# robot_board.net
KiCad netlist of a schematic drawn in EAGLE
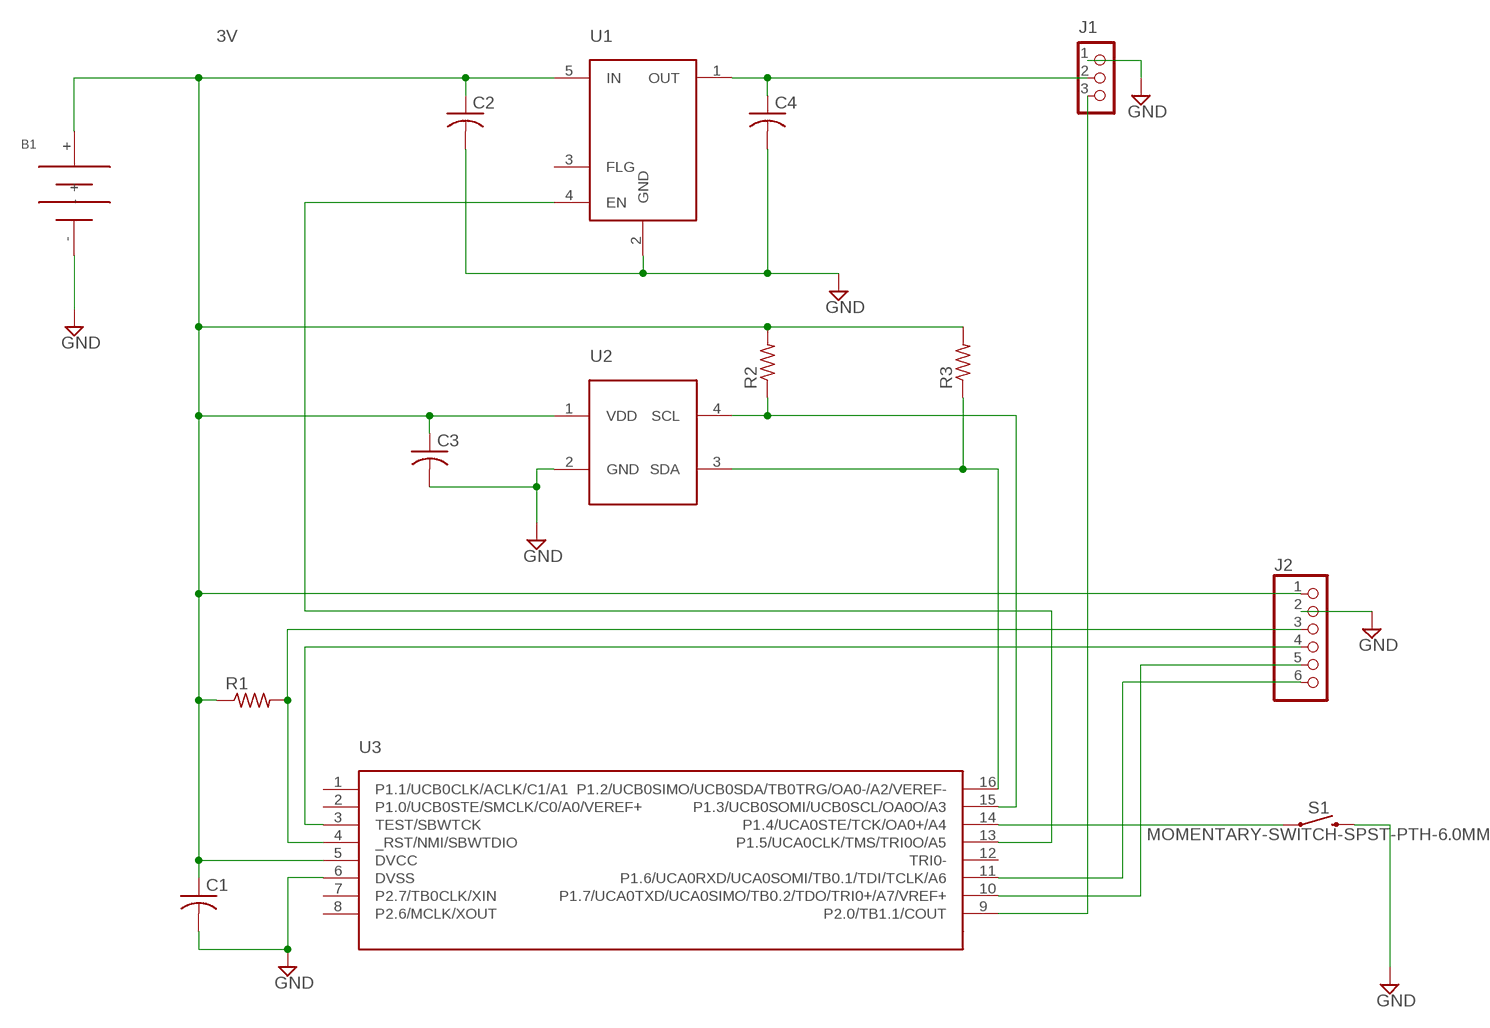
[diagram p0: schematic, sheet 1]

(export (version "E")
  (design (tool "Eeschema 10.0.6"))
  (components
    (comp (ref "B1")
      (value "2XAAA_HOLDER")
      (footprint "eagle-import:CHEAP_ASS_CHINESE_BH")
      (libsource (lib "eagle-import") (part "2XAAA_HOLDER"))
    )
    (comp (ref "C1")
      (value "C-USC0805")
      (footprint "eagle-import:C0805")
      (libsource (lib "eagle-import") (part "C-USC0805"))
    )
    (comp (ref "C2")
      (value "C-USC0805")
      (footprint "eagle-import:C0805")
      (libsource (lib "eagle-import") (part "C-USC0805"))
    )
    (comp (ref "C3")
      (value "C-USC0805")
      (footprint "eagle-import:C0805")
      (libsource (lib "eagle-import") (part "C-USC0805"))
    )
    (comp (ref "C4")
      (value "C-USC0805")
      (footprint "eagle-import:C0805")
      (libsource (lib "eagle-import") (part "C-USC0805"))
    )
    (comp (ref "J1")
      (value "CON_HEADER_1X03-PTH_RIGHT_ANGLED")
      (footprint "eagle-import:M1X3_MALE_RIGHT_ANGLED")
      (libsource (lib "eagle-import") (part "CON_HEADER_1X03-PTH_RIGHT_ANGLED"))
    )
    (comp (ref "J2")
      (value "PINHD-1X6")
      (footprint "eagle-import:1X06")
      (libsource (lib "eagle-import") (part "PINHD-1X6"))
    )
    (comp (ref "R1")
      (value "R-US_R0805")
      (footprint "eagle-import:R0805")
      (libsource (lib "eagle-import") (part "R-US_R0805"))
    )
    (comp (ref "R2")
      (value "R-US_R0805")
      (footprint "eagle-import:R0805")
      (libsource (lib "eagle-import") (part "R-US_R0805"))
    )
    (comp (ref "R3")
      (value "R-US_R0805")
      (footprint "eagle-import:R0805")
      (libsource (lib "eagle-import") (part "R-US_R0805"))
    )
    (comp (ref "S1")
      (value "MOMENTARY-SWITCH-SPST-PTH-6.0MM")
      (footprint "eagle-import:TACTILE_SWITCH_PTH_6.0MM")
      (libsource (lib "eagle-import") (part "MOMENTARY-SWITCH-SPST-PTH-6.0MM"))
    )
    (comp (ref "U1")
      (value "DI_AP22802AW5-7")
      (footprint "eagle-import:SOT-25")
      (libsource (lib "eagle-import") (part "DI_AP22802AW5-7"))
    )
    (comp (ref "U2")
      (value "LITE-ON_LTR-329ALS-01")
      (footprint "eagle-import:LITE-ON_LTR-329ALS-01")
      (libsource (lib "eagle-import") (part "LITE-ON_LTR-329ALS-01"))
    )
    (comp (ref "U3")
      (value "TI_MSP430FR2310IPW16R")
      (footprint "eagle-import:PW_R-PDSO-G16")
      (libsource (lib "eagle-import") (part "TI_MSP430FR2310IPW16R"))
    )
  )
  (nets
    (net (code "1") (name "/3V") (class "Default")
      (node (ref "B1") (pin "+") (pinfunction "+_+") (pintype "bidirectional"))
      (node (ref "C1") (pin "1") (pinfunction "1_1") (pintype "passive"))
      (node (ref "C2") (pin "1") (pinfunction "1_1") (pintype "passive"))
      (node (ref "C3") (pin "1") (pinfunction "1_1") (pintype "passive"))
      (node (ref "J2") (pin "1") (pinfunction "1_1") (pintype "passive"))
      (node (ref "R1") (pin "1") (pinfunction "1_1") (pintype "passive"))
      (node (ref "R2") (pin "2") (pinfunction "2_2") (pintype "passive"))
      (node (ref "R3") (pin "2") (pinfunction "2_2") (pintype "passive"))
      (node (ref "U1") (pin "5") (pinfunction "IN_5") (pintype "bidirectional"))
      (node (ref "U2") (pin "1") (pinfunction "VDD_1") (pintype "bidirectional"))
      (node (ref "U3") (pin "5") (pinfunction "DVCC_5") (pintype "bidirectional"))
    )
    (net (code "2") (name "GND") (class "Default")
      (node (ref "B1") (pin "-") (pinfunction "-_-") (pintype "bidirectional"))
      (node (ref "C1") (pin "2") (pinfunction "2_2") (pintype "passive"))
      (node (ref "C2") (pin "2") (pinfunction "2_2") (pintype "passive"))
      (node (ref "C3") (pin "2") (pinfunction "2_2") (pintype "passive"))
      (node (ref "C4") (pin "2") (pinfunction "2_2") (pintype "passive"))
      (node (ref "J1") (pin "1") (pinfunction "1_1") (pintype "bidirectional"))
      (node (ref "J2") (pin "2") (pinfunction "2_2") (pintype "passive"))
      (node (ref "S1") (pin "3") (pinfunction "2_3") (pintype "passive"))
      (node (ref "U1") (pin "2") (pinfunction "GND_2") (pintype "bidirectional"))
      (node (ref "U2") (pin "2") (pinfunction "GND_2") (pintype "bidirectional"))
      (node (ref "U3") (pin "6") (pinfunction "DVSS_6") (pintype "bidirectional"))
    )
    (net (code "3") (name "Net-(U1-EN)") (class "Default")
      (node (ref "U1") (pin "4") (pinfunction "EN_4") (pintype "bidirectional"))
      (node (ref "U3") (pin "13") (pinfunction "P1.5/UCA0CLK/TMS/TRI0O/A5_13") (pintype "bidirectional"))
    )
    (net (code "4") (name "Net-(U1-OUT)") (class "Default")
      (node (ref "C4") (pin "1") (pinfunction "1_1") (pintype "passive"))
      (node (ref "J1") (pin "2") (pinfunction "2_2") (pintype "bidirectional"))
      (node (ref "U1") (pin "1") (pinfunction "OUT_1") (pintype "bidirectional"))
    )
    (net (code "5") (name "Net-(U2-SCL)") (class "Default")
      (node (ref "R2") (pin "1") (pinfunction "1_1") (pintype "passive"))
      (node (ref "U2") (pin "4") (pinfunction "SCL_4") (pintype "bidirectional"))
      (node (ref "U3") (pin "15") (pinfunction "P1.3/UCB0SOMI/UCB0SCL/OA0O/A3_15") (pintype "bidirectional"))
    )
    (net (code "6") (name "Net-(U2-SDA)") (class "Default")
      (node (ref "R3") (pin "1") (pinfunction "1_1") (pintype "passive"))
      (node (ref "U2") (pin "3") (pinfunction "SDA_3") (pintype "bidirectional"))
      (node (ref "U3") (pin "16") (pinfunction "P1.2/UCB0SIMO/UCB0SDA/TB0TRG/OA0-/A2/VEREF-_16") (pintype "bidirectional"))
    )
    (net (code "7") (name "Net-(U3-P1.4{slash}UCA0STE{slash}TCK{slash}OA0+{slash}A4)") (class "Default")
      (node (ref "S1") (pin "1") (pinfunction "1_1") (pintype "passive"))
      (node (ref "U3") (pin "14") (pinfunction "P1.4/UCA0STE/TCK/OA0+/A4_14") (pintype "bidirectional"))
    )
    (net (code "8") (name "Net-(U3-P1.6{slash}UCA0RXD{slash}UCA0SOMI{slash}TB0.1{slash}TDI{slash}TCLK{slash}A6)") (class "Default")
      (node (ref "J2") (pin "6") (pinfunction "6_6") (pintype "passive"))
      (node (ref "U3") (pin "11") (pinfunction "P1.6/UCA0RXD/UCA0SOMI/TB0.1/TDI/TCLK/A6_11") (pintype "bidirectional"))
    )
    (net (code "9") (name "Net-(U3-P1.7{slash}UCA0TXD{slash}UCA0SIMO{slash}TB0.2{slash}TDO{slash}TRI0+{slash}A7{slash}VREF+)") (class "Default")
      (node (ref "J2") (pin "5") (pinfunction "5_5") (pintype "passive"))
      (node (ref "U3") (pin "10") (pinfunction "P1.7/UCA0TXD/UCA0SIMO/TB0.2/TDO/TRI0+/A7/VREF+_10") (pintype "bidirectional"))
    )
    (net (code "10") (name "Net-(U3-P2.0{slash}TB1.1{slash}COUT)") (class "Default")
      (node (ref "J1") (pin "3") (pinfunction "3_3") (pintype "bidirectional"))
      (node (ref "U3") (pin "9") (pinfunction "P2.0/TB1.1/COUT_9") (pintype "bidirectional"))
    )
    (net (code "11") (name "Net-(U3-TEST{slash}SBWTCK)") (class "Default")
      (node (ref "J2") (pin "4") (pinfunction "4_4") (pintype "passive"))
      (node (ref "U3") (pin "3") (pinfunction "TEST/SBWTCK_3") (pintype "bidirectional"))
    )
    (net (code "12") (name "Net-(U3-_RST{slash}NMI{slash}SBWTDIO)") (class "Default")
      (node (ref "J2") (pin "3") (pinfunction "3_3") (pintype "passive"))
      (node (ref "R1") (pin "2") (pinfunction "2_2") (pintype "passive"))
      (node (ref "U3") (pin "4") (pinfunction "_RST/NMI/SBWTDIO_4") (pintype "bidirectional"))
    )
    (net (code "13") (name "unconnected-(U1-FLG-Pad3)") (class "Default")
      (node (ref "U1") (pin "3") (pinfunction "FLG_3") (pintype "bidirectional"))
    )
    (net (code "14") (name "unconnected-(U3-P1.0{slash}UCB0STE{slash}SMCLK{slash}C0{slash}A0{slash}VEREF+-Pad2)") (class "Default")
      (node (ref "U3") (pin "2") (pinfunction "P1.0/UCB0STE/SMCLK/C0/A0/VEREF+_2") (pintype "bidirectional"))
    )
    (net (code "15") (name "unconnected-(U3-P1.1{slash}UCB0CLK{slash}ACLK{slash}C1{slash}A1-Pad1)") (class "Default")
      (node (ref "U3") (pin "1") (pinfunction "P1.1/UCB0CLK/ACLK/C1/A1_1") (pintype "bidirectional"))
    )
    (net (code "16") (name "unconnected-(U3-P2.6{slash}MCLK{slash}XOUT-Pad8)") (class "Default")
      (node (ref "U3") (pin "8") (pinfunction "P2.6/MCLK/XOUT_8") (pintype "bidirectional"))
    )
    (net (code "17") (name "unconnected-(U3-P2.7{slash}TB0CLK{slash}XIN-Pad7)") (class "Default")
      (node (ref "U3") (pin "7") (pinfunction "P2.7/TB0CLK/XIN_7") (pintype "bidirectional"))
    )
    (net (code "18") (name "unconnected-(U3-TRI0--Pad12)") (class "Default")
      (node (ref "U3") (pin "12") (pinfunction "TRI0-_12") (pintype "bidirectional"))
    )
  )
)
